# mainboard.net
KiCad netlist of a schematic drawn in EAGLE
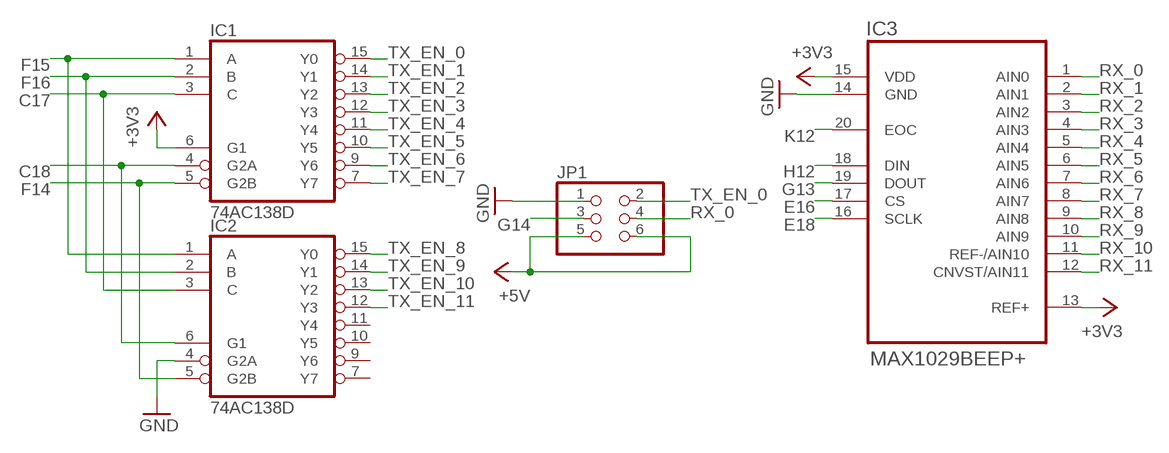
[diagram p0: schematic, sheet 1]
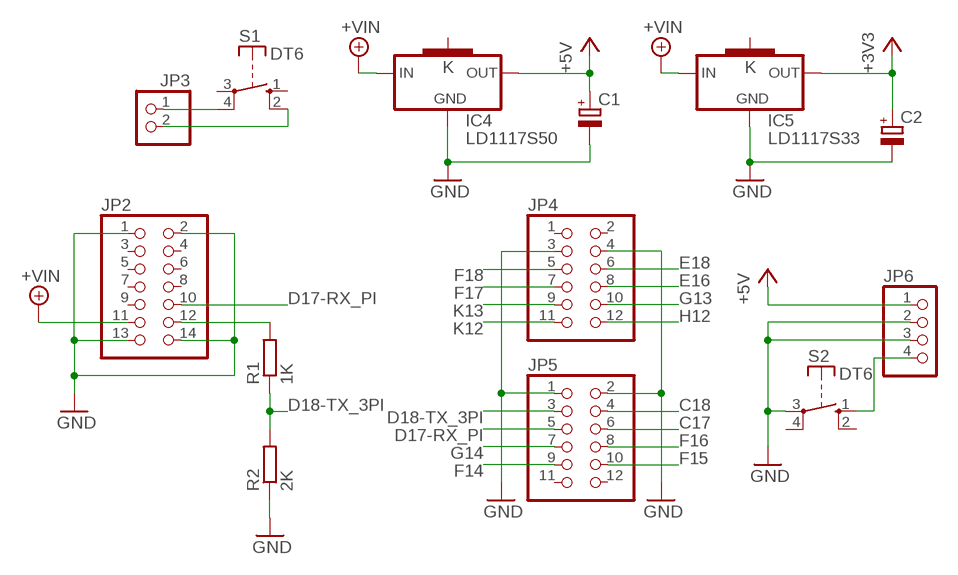
[diagram p1: schematic, sheet 2]

(export (version "E")
  (design (tool "Eeschema 10.0.6"))
  (components
    (comp (ref "IC1")
      (value "74AC138D")
      (footprint "eagle-import:SO16")
      (libsource (lib "eagle-import") (part "74138DAC"))
    )
    (comp (ref "IC2")
      (value "74AC138D")
      (footprint "eagle-import:SO16")
      (libsource (lib "eagle-import") (part "74138DAC"))
    )
    (comp (ref "IC3")
      (value "MAX1029BEEP+")
      (footprint "eagle-import:SOP64P600X165-20N")
      (libsource (lib "eagle-import") (part "MAX1029BEEP+"))
    )
    (comp (ref "JP1")
      (value "PINHD-2X3")
      (footprint "eagle-import:2X03")
      (libsource (lib "eagle-import") (part "PINHD-2X3"))
    )
    (comp (ref "C1")
      (value "CPOL-EUE2.5-5")
      (footprint "eagle-import:E2,5-5")
      (libsource (lib "eagle-import") (part "CPOL-EUE2.5-5"))
    )
    (comp (ref "C2")
      (value "CPOL-EUE2.5-5")
      (footprint "eagle-import:E2,5-5")
      (libsource (lib "eagle-import") (part "CPOL-EUE2.5-5"))
    )
    (comp (ref "IC4")
      (value "LD1117S50")
      (footprint "eagle-import:SOT223")
      (libsource (lib "eagle-import") (part "LD1117S50"))
    )
    (comp (ref "IC5")
      (value "LD1117S33")
      (footprint "eagle-import:SOT223")
      (libsource (lib "eagle-import") (part "LD1117S33"))
    )
    (comp (ref "JP2")
      (value "PINHD-2X7")
      (footprint "eagle-import:2X07")
      (libsource (lib "eagle-import") (part "PINHD-2X7"))
    )
    (comp (ref "JP3")
      (value "PINHD-1X2")
      (footprint "eagle-import:1X02")
      (libsource (lib "eagle-import") (part "PINHD-1X2"))
    )
    (comp (ref "JP4")
      (value "PINHD-2X6")
      (footprint "eagle-import:2X06")
      (libsource (lib "eagle-import") (part "PINHD-2X6"))
    )
    (comp (ref "JP5")
      (value "PINHD-2X6")
      (footprint "eagle-import:2X06")
      (libsource (lib "eagle-import") (part "PINHD-2X6"))
    )
    (comp (ref "JP6")
      (value "PINHD-1X4")
      (footprint "eagle-import:1X04")
      (libsource (lib "eagle-import") (part "PINHD-1X4"))
    )
    (comp (ref "R1")
      (value "1K")
      (footprint "eagle-import:R0805")
      (libsource (lib "eagle-import") (part "R-EU_R0805"))
    )
    (comp (ref "R2")
      (value "2K")
      (footprint "eagle-import:R0805")
      (libsource (lib "eagle-import") (part "R-EU_R0805"))
    )
    (comp (ref "S1")
      (value "DT6")
      (footprint "eagle-import:DT6")
      (libsource (lib "eagle-import") (part "DT6"))
    )
    (comp (ref "S2")
      (value "DT6")
      (footprint "eagle-import:DT6")
      (libsource (lib "eagle-import") (part "DT6"))
    )
  )
  (nets
    (net (code "1") (name "+3V3") (class "Default")
      (node (ref "C2") (pin "+") (pinfunction "+_+") (pintype "passive"))
      (node (ref "IC1") (pin "6") (pinfunction "G1_6") (pintype "input"))
      (node (ref "IC3") (pin "13") (pinfunction "REF+_13") (pintype "input"))
      (node (ref "IC3") (pin "15") (pinfunction "VDD_15") (pintype "power_in"))
      (node (ref "IC5") (pin "2") (pinfunction "OUT_2") (pintype "passive"))
    )
    (net (code "2") (name "+5V") (class "Default")
      (node (ref "C1") (pin "+") (pinfunction "+_+") (pintype "passive"))
      (node (ref "IC4") (pin "2") (pinfunction "OUT_2") (pintype "passive"))
      (node (ref "JP1") (pin "5") (pinfunction "5_5") (pintype "passive"))
      (node (ref "JP1") (pin "6") (pinfunction "6_6") (pintype "passive"))
      (node (ref "JP6") (pin "1") (pinfunction "1_1") (pintype "passive"))
    )
    (net (code "3") (name "+VIN") (class "Default")
      (node (ref "IC4") (pin "3") (pinfunction "IN_3") (pintype "input"))
      (node (ref "IC5") (pin "3") (pinfunction "IN_3") (pintype "input"))
      (node (ref "JP2") (pin "11") (pinfunction "11_11") (pintype "passive"))
    )
    (net (code "4") (name "C17") (class "Default")
      (node (ref "IC1") (pin "3") (pinfunction "C_3") (pintype "input"))
      (node (ref "IC2") (pin "3") (pinfunction "C_3") (pintype "input"))
      (node (ref "JP5") (pin "6") (pinfunction "6_6") (pintype "passive"))
    )
    (net (code "5") (name "C18") (class "Default")
      (node (ref "IC1") (pin "4") (pinfunction "G2A_4") (pintype "input"))
      (node (ref "IC2") (pin "6") (pinfunction "G1_6") (pintype "input"))
      (node (ref "JP5") (pin "4") (pinfunction "4_4") (pintype "passive"))
    )
    (net (code "6") (name "D17-RX_PI") (class "Default")
      (node (ref "JP2") (pin "10") (pinfunction "10_10") (pintype "passive"))
      (node (ref "JP5") (pin "5") (pinfunction "5_5") (pintype "passive"))
    )
    (net (code "7") (name "D18-TX_3PI") (class "Default")
      (node (ref "JP5") (pin "3") (pinfunction "3_3") (pintype "passive"))
      (node (ref "R1") (pin "1") (pinfunction "1_1") (pintype "passive"))
      (node (ref "R2") (pin "2") (pinfunction "2_2") (pintype "passive"))
    )
    (net (code "8") (name "E16") (class "Default")
      (node (ref "IC3") (pin "17") (pinfunction "CS_17") (pintype "input"))
      (node (ref "JP4") (pin "8") (pinfunction "8_8") (pintype "passive"))
    )
    (net (code "9") (name "E18") (class "Default")
      (node (ref "IC3") (pin "16") (pinfunction "SCLK_16") (pintype "input"))
      (node (ref "JP4") (pin "6") (pinfunction "6_6") (pintype "passive"))
    )
    (net (code "10") (name "F14") (class "Default")
      (node (ref "IC1") (pin "5") (pinfunction "G2B_5") (pintype "input"))
      (node (ref "IC2") (pin "5") (pinfunction "G2B_5") (pintype "input"))
      (node (ref "JP5") (pin "9") (pinfunction "9_9") (pintype "passive"))
    )
    (net (code "11") (name "F15") (class "Default")
      (node (ref "IC1") (pin "1") (pinfunction "A_1") (pintype "input"))
      (node (ref "IC2") (pin "1") (pinfunction "A_1") (pintype "input"))
      (node (ref "JP5") (pin "10") (pinfunction "10_10") (pintype "passive"))
    )
    (net (code "12") (name "F16") (class "Default")
      (node (ref "IC1") (pin "2") (pinfunction "B_2") (pintype "input"))
      (node (ref "IC2") (pin "2") (pinfunction "B_2") (pintype "input"))
      (node (ref "JP5") (pin "8") (pinfunction "8_8") (pintype "passive"))
    )
    (net (code "13") (name "F17") (class "Default")
      (node (ref "JP4") (pin "7") (pinfunction "7_7") (pintype "passive"))
    )
    (net (code "14") (name "F18") (class "Default")
      (node (ref "JP4") (pin "5") (pinfunction "5_5") (pintype "passive"))
    )
    (net (code "15") (name "G13") (class "Default")
      (node (ref "IC3") (pin "19") (pinfunction "DOUT_19") (pintype "output"))
      (node (ref "JP4") (pin "10") (pinfunction "10_10") (pintype "passive"))
    )
    (net (code "16") (name "G14") (class "Default")
      (node (ref "JP1") (pin "3") (pinfunction "3_3") (pintype "passive"))
      (node (ref "JP5") (pin "7") (pinfunction "7_7") (pintype "passive"))
    )
    (net (code "17") (name "GND") (class "Default")
      (node (ref "C1") (pin "-") (pinfunction "-_-") (pintype "passive"))
      (node (ref "C2") (pin "-") (pinfunction "-_-") (pintype "passive"))
      (node (ref "IC2") (pin "4") (pinfunction "G2A_4") (pintype "input"))
      (node (ref "IC3") (pin "14") (pinfunction "GND_14") (pintype "power_in"))
      (node (ref "IC4") (pin "1") (pinfunction "GND_1") (pintype "input"))
      (node (ref "IC5") (pin "1") (pinfunction "GND_1") (pintype "input"))
      (node (ref "JP1") (pin "1") (pinfunction "1_1") (pintype "passive"))
      (node (ref "JP2") (pin "1") (pinfunction "1_1") (pintype "passive"))
      (node (ref "JP2") (pin "13") (pinfunction "13_13") (pintype "passive"))
      (node (ref "JP2") (pin "14") (pinfunction "14_14") (pintype "passive"))
      (node (ref "JP2") (pin "2") (pinfunction "2_2") (pintype "passive"))
      (node (ref "JP4") (pin "3") (pinfunction "3_3") (pintype "passive"))
      (node (ref "JP4") (pin "4") (pinfunction "4_4") (pintype "passive"))
      (node (ref "JP5") (pin "1") (pinfunction "1_1") (pintype "passive"))
      (node (ref "JP5") (pin "2") (pinfunction "2_2") (pintype "passive"))
      (node (ref "JP6") (pin "2") (pinfunction "2_2") (pintype "passive"))
      (node (ref "JP6") (pin "3") (pinfunction "3_3") (pintype "passive"))
      (node (ref "R2") (pin "1") (pinfunction "1_1") (pintype "passive"))
      (node (ref "S2") (pin "3") (pinfunction "P_3") (pintype "passive"))
    )
    (net (code "18") (name "H12") (class "Default")
      (node (ref "IC3") (pin "18") (pinfunction "DIN_18") (pintype "input"))
      (node (ref "JP4") (pin "12") (pinfunction "12_12") (pintype "passive"))
    )
    (net (code "19") (name "K12") (class "Default")
      (node (ref "IC3") (pin "20") (pinfunction "EOC_20") (pintype "output"))
      (node (ref "JP4") (pin "11") (pinfunction "11_11") (pintype "passive"))
    )
    (net (code "20") (name "K13") (class "Default")
      (node (ref "JP4") (pin "9") (pinfunction "9_9") (pintype "passive"))
    )
    (net (code "21") (name "Net-(JP2-Pad12)") (class "Default")
      (node (ref "JP2") (pin "12") (pinfunction "12_12") (pintype "passive"))
      (node (ref "R1") (pin "2") (pinfunction "2_2") (pintype "passive"))
    )
    (net (code "22") (name "Net-(JP3-Pad1)") (class "Default")
      (node (ref "JP3") (pin "1") (pinfunction "1_1") (pintype "passive"))
      (node (ref "S1") (pin "4") (pinfunction "P_4") (pintype "passive"))
    )
    (net (code "23") (name "Net-(JP3-Pad2)") (class "Default")
      (node (ref "JP3") (pin "2") (pinfunction "2_2") (pintype "passive"))
      (node (ref "S1") (pin "2") (pinfunction "S_2") (pintype "passive"))
    )
    (net (code "24") (name "Net-(JP6-Pad4)") (class "Default")
      (node (ref "JP6") (pin "4") (pinfunction "4_4") (pintype "passive"))
      (node (ref "S2") (pin "1") (pinfunction "S_1") (pintype "passive"))
    )
    (net (code "25") (name "RX_0") (class "Default")
      (node (ref "IC3") (pin "1") (pinfunction "AIN0_1") (pintype "input"))
      (node (ref "JP1") (pin "4") (pinfunction "4_4") (pintype "passive"))
    )
    (net (code "26") (name "RX_1") (class "Default")
      (node (ref "IC3") (pin "2") (pinfunction "AIN1_2") (pintype "input"))
    )
    (net (code "27") (name "RX_2") (class "Default")
      (node (ref "IC3") (pin "3") (pinfunction "AIN2_3") (pintype "input"))
    )
    (net (code "28") (name "RX_3") (class "Default")
      (node (ref "IC3") (pin "4") (pinfunction "AIN3_4") (pintype "input"))
    )
    (net (code "29") (name "RX_4") (class "Default")
      (node (ref "IC3") (pin "5") (pinfunction "AIN4_5") (pintype "input"))
    )
    (net (code "30") (name "RX_5") (class "Default")
      (node (ref "IC3") (pin "6") (pinfunction "AIN5_6") (pintype "input"))
    )
    (net (code "31") (name "RX_6") (class "Default")
      (node (ref "IC3") (pin "7") (pinfunction "AIN6_7") (pintype "input"))
    )
    (net (code "32") (name "RX_7") (class "Default")
      (node (ref "IC3") (pin "8") (pinfunction "AIN7_8") (pintype "input"))
    )
    (net (code "33") (name "RX_8") (class "Default")
      (node (ref "IC3") (pin "9") (pinfunction "AIN8_9") (pintype "input"))
    )
    (net (code "34") (name "RX_9") (class "Default")
      (node (ref "IC3") (pin "10") (pinfunction "AIN9_10") (pintype "input"))
    )
    (net (code "35") (name "RX_10") (class "Default")
      (node (ref "IC3") (pin "11") (pinfunction "REF-/AIN10_11") (pintype "input"))
    )
    (net (code "36") (name "RX_11") (class "Default")
      (node (ref "IC3") (pin "12") (pinfunction "CNVST/AIN11_12") (pintype "input"))
    )
    (net (code "37") (name "TX_EN_0") (class "Default")
      (node (ref "IC1") (pin "15") (pinfunction "Y0_15") (pintype "output"))
      (node (ref "JP1") (pin "2") (pinfunction "2_2") (pintype "passive"))
    )
    (net (code "38") (name "TX_EN_1") (class "Default")
      (node (ref "IC1") (pin "14") (pinfunction "Y1_14") (pintype "output"))
    )
    (net (code "39") (name "TX_EN_2") (class "Default")
      (node (ref "IC1") (pin "13") (pinfunction "Y2_13") (pintype "output"))
    )
    (net (code "40") (name "TX_EN_3") (class "Default")
      (node (ref "IC1") (pin "12") (pinfunction "Y3_12") (pintype "output"))
    )
    (net (code "41") (name "TX_EN_4") (class "Default")
      (node (ref "IC1") (pin "11") (pinfunction "Y4_11") (pintype "output"))
    )
    (net (code "42") (name "TX_EN_5") (class "Default")
      (node (ref "IC1") (pin "10") (pinfunction "Y5_10") (pintype "output"))
    )
    (net (code "43") (name "TX_EN_6") (class "Default")
      (node (ref "IC1") (pin "9") (pinfunction "Y6_9") (pintype "output"))
    )
    (net (code "44") (name "TX_EN_7") (class "Default")
      (node (ref "IC1") (pin "7") (pinfunction "Y7_7") (pintype "output"))
    )
    (net (code "45") (name "TX_EN_8") (class "Default")
      (node (ref "IC2") (pin "15") (pinfunction "Y0_15") (pintype "output"))
    )
    (net (code "46") (name "TX_EN_9") (class "Default")
      (node (ref "IC2") (pin "14") (pinfunction "Y1_14") (pintype "output"))
    )
    (net (code "47") (name "TX_EN_10") (class "Default")
      (node (ref "IC2") (pin "13") (pinfunction "Y2_13") (pintype "output"))
    )
    (net (code "48") (name "TX_EN_11") (class "Default")
      (node (ref "IC2") (pin "12") (pinfunction "Y3_12") (pintype "output"))
    )
    (net (code "49") (name "unconnected-(IC2A-Y4-Pad11)") (class "Default")
      (node (ref "IC2") (pin "11") (pinfunction "Y4_11") (pintype "output"))
    )
    (net (code "50") (name "unconnected-(IC2A-Y5-Pad10)") (class "Default")
      (node (ref "IC2") (pin "10") (pinfunction "Y5_10") (pintype "output"))
    )
    (net (code "51") (name "unconnected-(IC2A-Y6-Pad9)") (class "Default")
      (node (ref "IC2") (pin "9") (pinfunction "Y6_9") (pintype "output"))
    )
    (net (code "52") (name "unconnected-(IC2A-Y7-Pad7)") (class "Default")
      (node (ref "IC2") (pin "7") (pinfunction "Y7_7") (pintype "output"))
    )
    (net (code "53") (name "unconnected-(IC4-K-Pad4)") (class "Default")
      (node (ref "IC4") (pin "4") (pinfunction "K_4") (pintype "passive"))
    )
    (net (code "54") (name "unconnected-(IC5-K-Pad4)") (class "Default")
      (node (ref "IC5") (pin "4") (pinfunction "K_4") (pintype "passive"))
    )
    (net (code "55") (name "unconnected-(JP2-Pad3)") (class "Default")
      (node (ref "JP2") (pin "3") (pinfunction "3_3") (pintype "passive"))
    )
    (net (code "56") (name "unconnected-(JP2-Pad4)") (class "Default")
      (node (ref "JP2") (pin "4") (pinfunction "4_4") (pintype "passive"))
    )
    (net (code "57") (name "unconnected-(JP2-Pad5)") (class "Default")
      (node (ref "JP2") (pin "5") (pinfunction "5_5") (pintype "passive"))
    )
    (net (code "58") (name "unconnected-(JP2-Pad6)") (class "Default")
      (node (ref "JP2") (pin "6") (pinfunction "6_6") (pintype "passive"))
    )
    (net (code "59") (name "unconnected-(JP2-Pad7)") (class "Default")
      (node (ref "JP2") (pin "7") (pinfunction "7_7") (pintype "passive"))
    )
    (net (code "60") (name "unconnected-(JP2-Pad8)") (class "Default")
      (node (ref "JP2") (pin "8") (pinfunction "8_8") (pintype "passive"))
    )
    (net (code "61") (name "unconnected-(JP2-Pad9)") (class "Default")
      (node (ref "JP2") (pin "9") (pinfunction "9_9") (pintype "passive"))
    )
    (net (code "62") (name "unconnected-(JP4-Pad1)") (class "Default")
      (node (ref "JP4") (pin "1") (pinfunction "1_1") (pintype "passive"))
    )
    (net (code "63") (name "unconnected-(JP4-Pad2)") (class "Default")
      (node (ref "JP4") (pin "2") (pinfunction "2_2") (pintype "passive"))
    )
    (net (code "64") (name "unconnected-(JP5-Pad11)") (class "Default")
      (node (ref "JP5") (pin "11") (pinfunction "11_11") (pintype "passive"))
    )
    (net (code "65") (name "unconnected-(JP5-Pad12)") (class "Default")
      (node (ref "JP5") (pin "12") (pinfunction "12_12") (pintype "passive"))
    )
    (net (code "66") (name "unconnected-(S1-P-Pad3)") (class "Default")
      (node (ref "S1") (pin "3") (pinfunction "P_3") (pintype "passive"))
    )
    (net (code "67") (name "unconnected-(S1-S-Pad1)") (class "Default")
      (node (ref "S1") (pin "1") (pinfunction "S_1") (pintype "passive"))
    )
    (net (code "68") (name "unconnected-(S2-P-Pad4)") (class "Default")
      (node (ref "S2") (pin "4") (pinfunction "P_4") (pintype "passive"))
    )
    (net (code "69") (name "unconnected-(S2-S-Pad2)") (class "Default")
      (node (ref "S2") (pin "2") (pinfunction "S_2") (pintype "passive"))
    )
  )
)
